# TopLevelSchem.net
KiCad netlist of a schematic drawn in Altium Designer
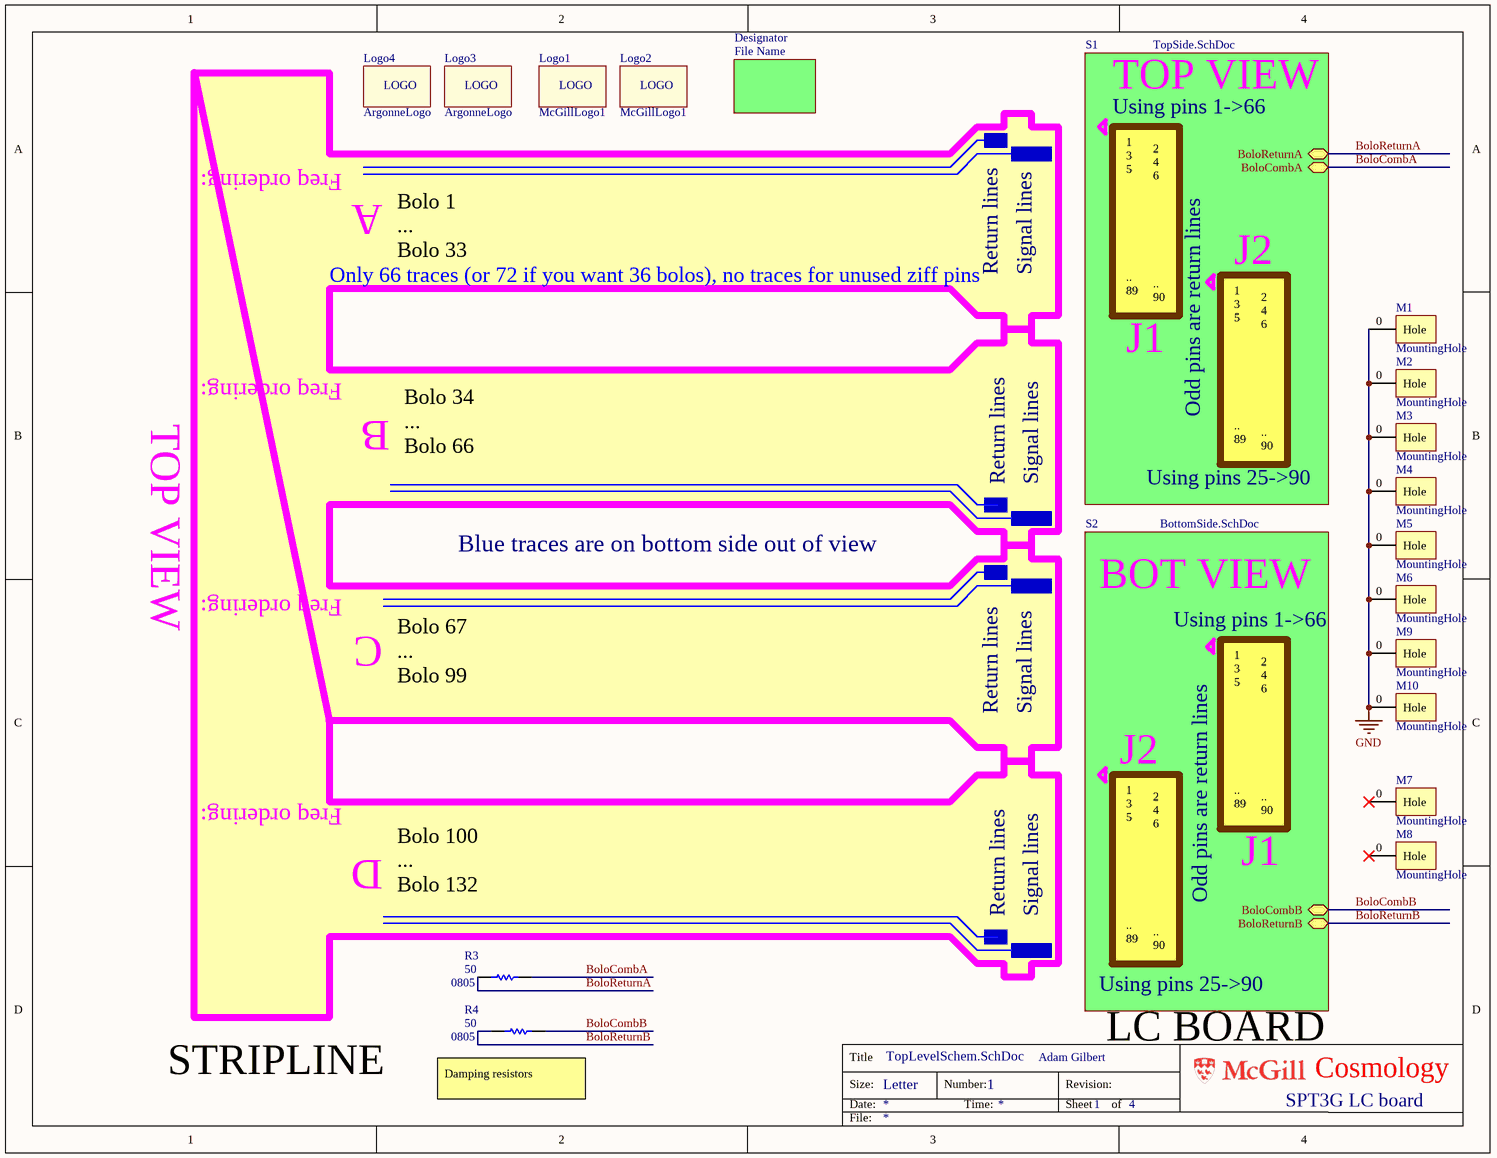
[diagram p0: TopLevelSchem.SchDoc]

(export (version "E")
  (design (tool "Eeschema 10.0.6"))
  (components
    (comp (ref "Logo1")
      (value "McGillLogo1")
      (footprint "McGillLogo1")
      (libsource (lib "SPT3G_LCBoard") (part "Logo"))
    )
    (comp (ref "Logo2")
      (value "McGillLogo1")
      (footprint "McGillLogo1")
      (libsource (lib "SPT3G_LCBoard") (part "Logo"))
    )
    (comp (ref "Logo3")
      (value "ArgonneLogo")
      (footprint "ArgonneLogo")
      (libsource (lib "SPT3G_AdapterBoard") (part "Logo"))
    )
    (comp (ref "Logo4")
      (value "ArgonneLogo")
      (footprint "ArgonneLogo")
      (libsource (lib "SPT3G_AdapterBoard") (part "Logo"))
    )
    (comp (ref "M1")
      (value "MountingHole")
      (footprint "MountingHole")
      (libsource (lib "SPT3G_LCBoard") (part "MountingHole"))
    )
    (comp (ref "M2")
      (value "MountingHole")
      (footprint "MountingHole")
      (libsource (lib "SPT3G_LCBoard") (part "MountingHole"))
    )
    (comp (ref "M3")
      (value "MountingHole")
      (footprint "MountingHole")
      (libsource (lib "SPT3G_LCBoard") (part "MountingHole"))
    )
    (comp (ref "M4")
      (value "MountingHole")
      (footprint "MountingHole")
      (libsource (lib "SPT3G_LCBoard") (part "MountingHole"))
    )
    (comp (ref "M5")
      (value "MountingHole")
      (footprint "MountingHole")
      (libsource (lib "SPT3G_LCBoard") (part "MountingHole"))
    )
    (comp (ref "M6")
      (value "MountingHole")
      (footprint "MountingHole")
      (libsource (lib "SPT3G_LCBoard") (part "MountingHole"))
    )
    (comp (ref "M7")
      (value "MountingHole")
      (footprint "MountingHole")
      (libsource (lib "SPT3G_LCBoard") (part "MountingHole"))
    )
    (comp (ref "M8")
      (value "MountingHole")
      (footprint "MountingHole")
      (libsource (lib "SPT3G_LCBoard") (part "MountingHole"))
    )
    (comp (ref "M9")
      (value "MountingHole")
      (footprint "MountingHole")
      (libsource (lib "SPT3G_LCBoard") (part "MountingHole"))
    )
    (comp (ref "M10")
      (value "MountingHole")
      (footprint "MountingHole")
      (libsource (lib "SPT3G_LCBoard") (part "MountingHole"))
    )
    (comp (ref "R3")
      (value "50")
      (footprint "0805")
      (description "Resistor")
      (libsource (lib "SPT3G_LCBoard") (part "Res1206"))
    )
    (comp (ref "R4")
      (value "50")
      (footprint "0805")
      (description "Resistor")
      (libsource (lib "SPT3G_LCBoard") (part "Res1206"))
    )
  )
  (nets
    (net (code "1") (name "/BoloCombA") (class "Default")
      (node (ref "R3") (pin "1") (pinfunction "1_1") (pintype "passive"))
    )
    (net (code "2") (name "/BoloCombB") (class "Default")
      (node (ref "R4") (pin "1") (pinfunction "1_1") (pintype "passive"))
    )
    (net (code "3") (name "/BoloReturnA") (class "Default")
      (node (ref "R3") (pin "2") (pinfunction "2_2") (pintype "passive"))
    )
    (net (code "4") (name "/BoloReturnB") (class "Default")
      (node (ref "R4") (pin "2") (pinfunction "2_2") (pintype "passive"))
    )
    (net (code "5") (name "GND") (class "Default")
      (node (ref "M1") (pin "0") (pinfunction "Hole_0") (pintype "passive"))
      (node (ref "M10") (pin "0") (pinfunction "Hole_0") (pintype "passive"))
      (node (ref "M2") (pin "0") (pinfunction "Hole_0") (pintype "passive"))
      (node (ref "M3") (pin "0") (pinfunction "Hole_0") (pintype "passive"))
      (node (ref "M4") (pin "0") (pinfunction "Hole_0") (pintype "passive"))
      (node (ref "M5") (pin "0") (pinfunction "Hole_0") (pintype "passive"))
      (node (ref "M6") (pin "0") (pinfunction "Hole_0") (pintype "passive"))
      (node (ref "M9") (pin "0") (pinfunction "Hole_0") (pintype "passive"))
    )
    (net (code "6") (name "unconnected-(M7-Hole-Pad0)") (class "Default")
      (node (ref "M7") (pin "0") (pinfunction "Hole_0") (pintype "passive+no_connect"))
    )
    (net (code "7") (name "unconnected-(M8-Hole-Pad0)") (class "Default")
      (node (ref "M8") (pin "0") (pinfunction "Hole_0") (pintype "passive+no_connect"))
    )
  )
)
